# therm-hub.net
KiCad netlist of a schematic drawn in EasyEDA
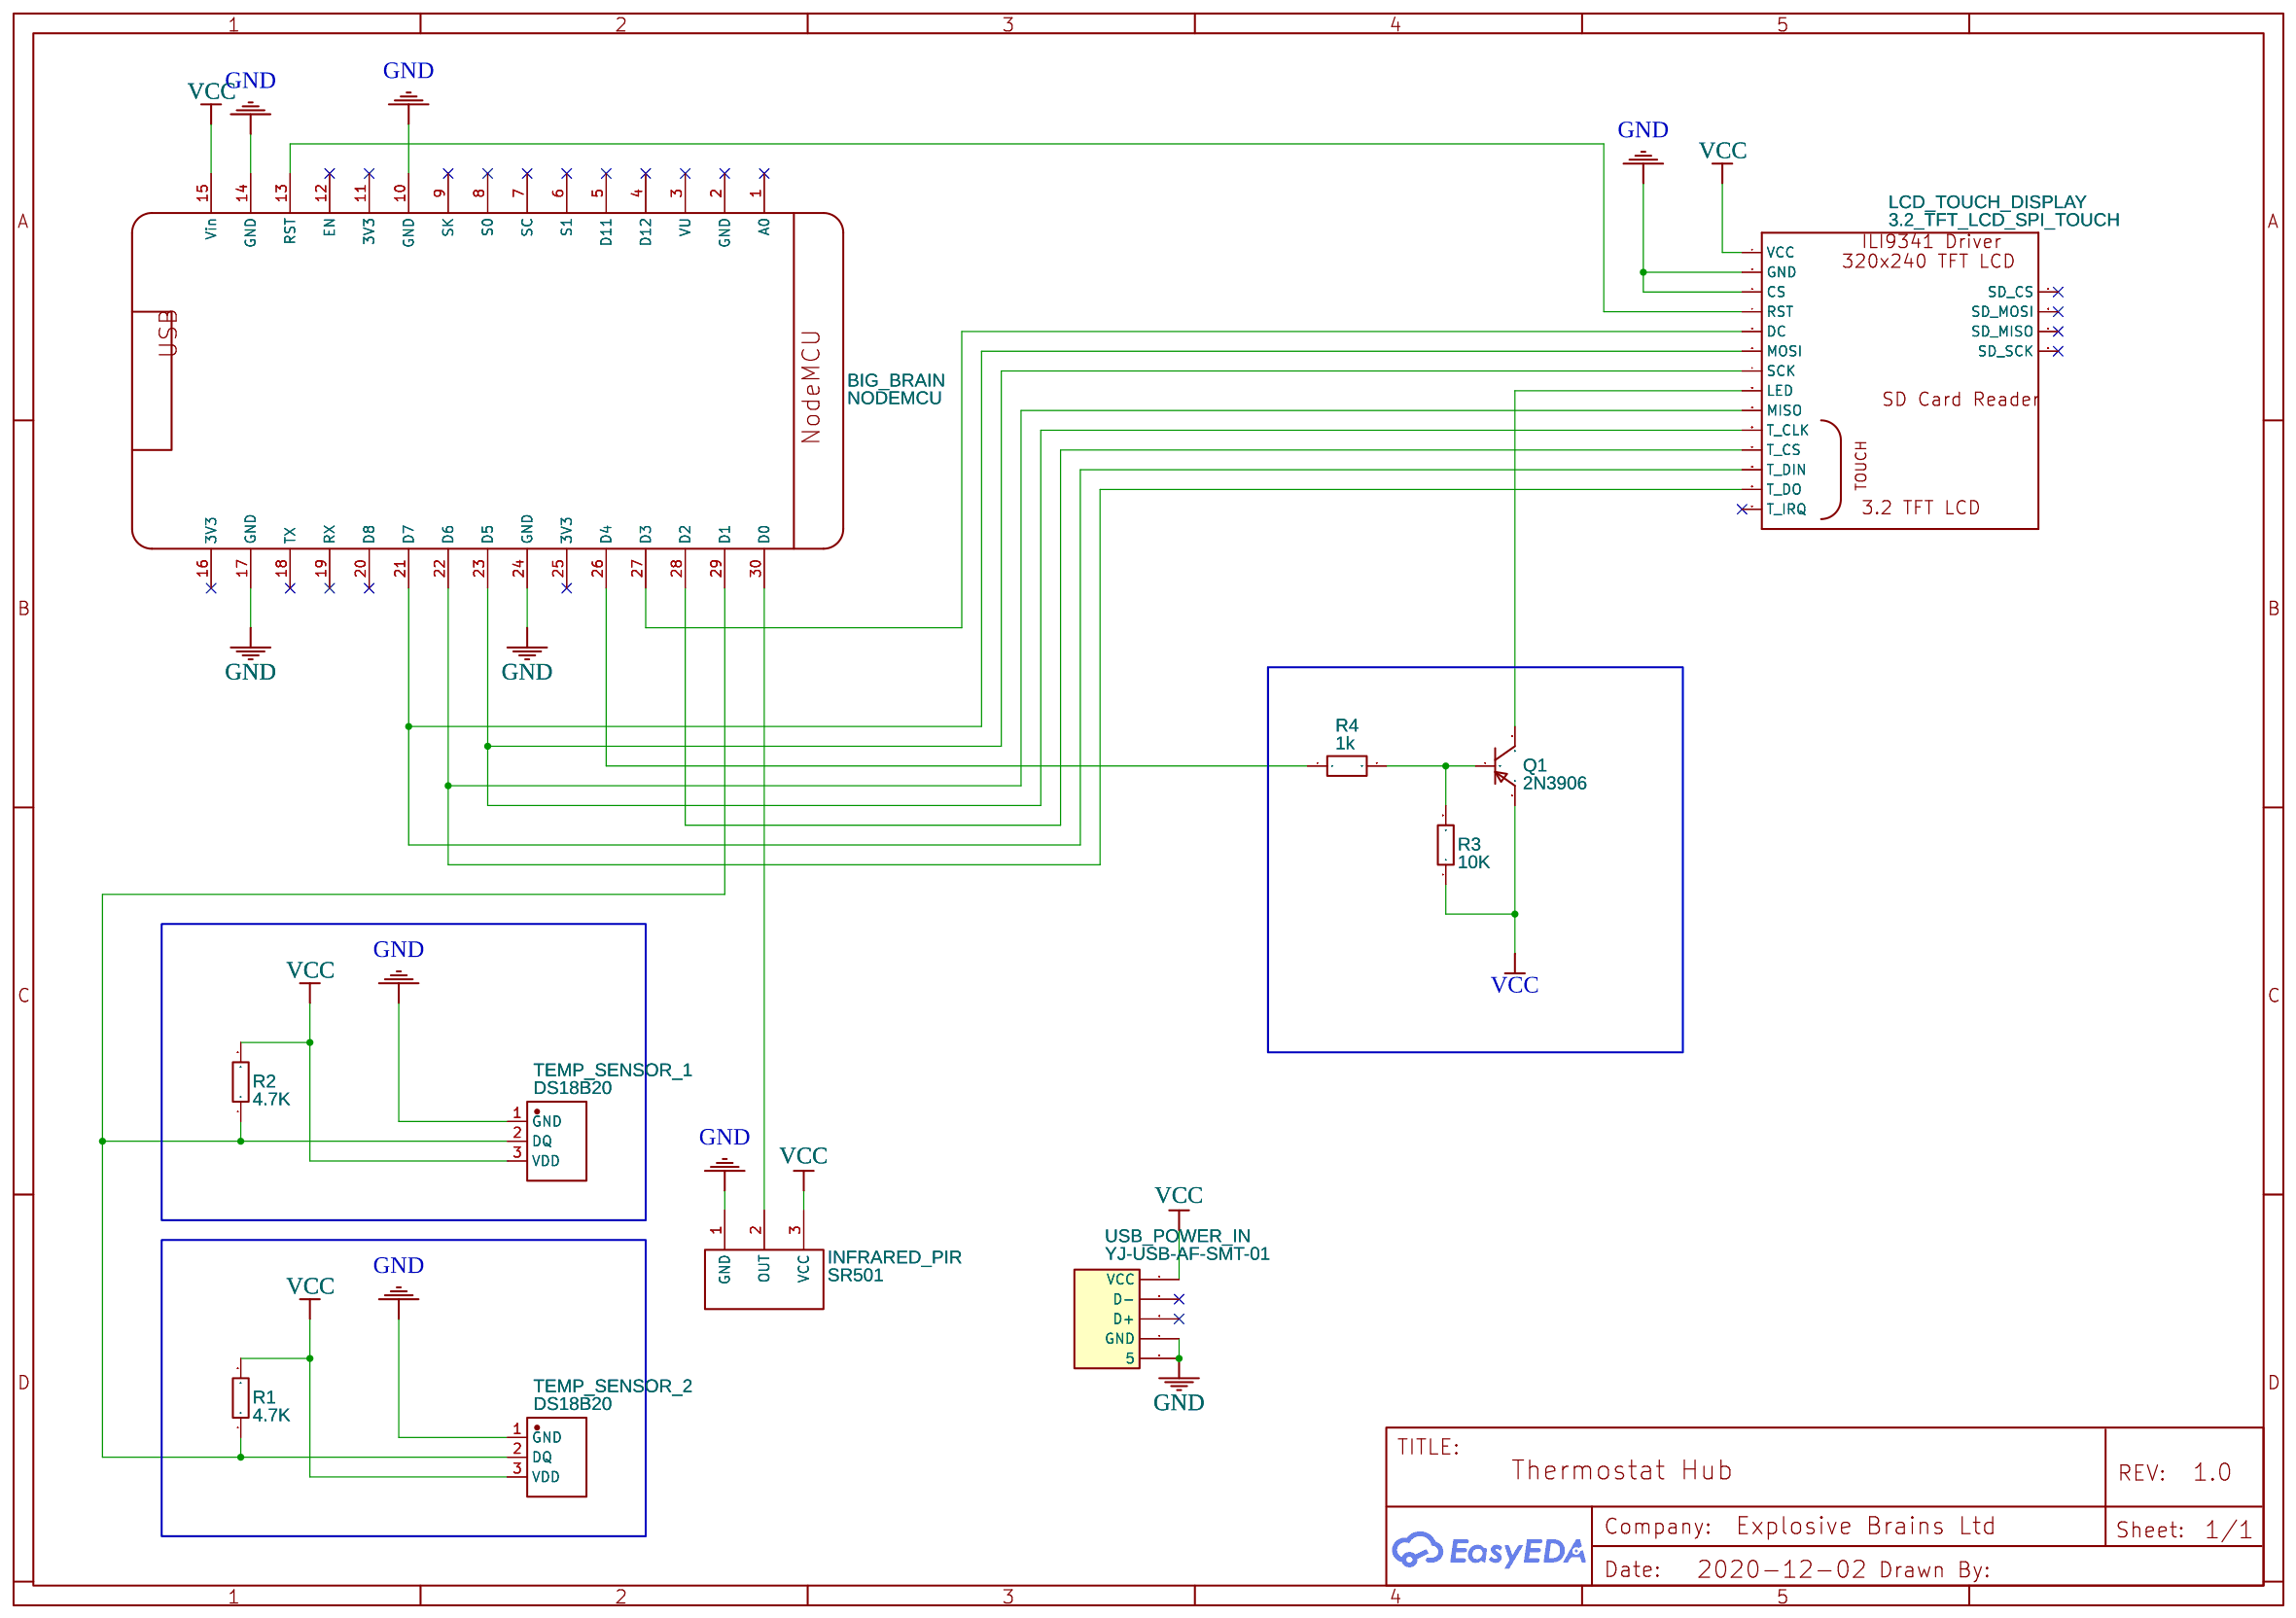
[diagram p0: schematic sheet]

(export (version "E")
  (design (tool "Eeschema 10.0.6"))
  (components
    (comp (ref "BIG_BRAIN") (value "NODEMCU") (libsource (lib "") (part "NODEMCU")))
    (comp (ref "INFRARED_PIR") (value "SR501") (libsource (lib "") (part "SR501")))
    (comp (ref "LCD_TOUCH_DISPLAY")
      (value "3.2_TFT_LCD_SPI_TOUCH")
      (libsource (lib "") (part "3.2_TFT_LCD_SPI_TOUCH"))
    )
    (comp (ref "Q1")
      (value "2N3906")
      (fields (field (name "BOM_Supplier Part") "C9809"))
      (libsource (lib "") (part "2N3906"))
    )
    (comp (ref "R1")
      (value "4.7K")
      (fields (field (name "BOM_Supplier Part") "C120071"))
      (libsource (lib "") (part "CF1/4W-4.7KΩ±5% T52"))
    )
    (comp (ref "R2")
      (value "4.7K")
      (fields (field (name "BOM_Supplier Part") "C120071"))
      (libsource (lib "") (part "CF1/4W-4.7KΩ±5% T52"))
    )
    (comp (ref "R3")
      (value "10K")
      (fields
        (field (name "BOM_Manufacturer Part") "CFR0W4J0103A50")
        (field (name "BOM_Supplier Part") "C61299")
      )
      (libsource (lib "") (part "CFR0W4J0103A50"))
    )
    (comp (ref "R4")
      (value "1k")
      (fields
        (field (name "BOM_Manufacturer Part") "CFR0W4J0102A50")
        (field (name "BOM_Supplier Part") "C66649")
      )
      (libsource (lib "") (part "CFR0W4J0102A50_C66649"))
    )
    (comp (ref "TEMP_SENSOR_1")
      (value "DS18B20")
      (fields (field (name "BOM_Supplier Part") "C376006"))
      (libsource (lib "") (part "DS18B20"))
    )
    (comp (ref "TEMP_SENSOR_2")
      (value "DS18B20")
      (fields (field (name "BOM_Supplier Part") "C376006"))
      (libsource (lib "") (part "DS18B20"))
    )
    (comp (ref "USB_POWER_IN")
      (value "YJ-USB-AF-SMT-01")
      (fields (field (name "BOM_Supplier Part") "C8328"))
      (libsource (lib "") (part "YJ-USB-AF-SMT-01"))
    )
  )
  (nets
    (net (code "1") (name "GND") (class "Default")
      (node (ref "BIG_BRAIN") (pin "10") (pinfunction "GND_10") (pintype "unspecified"))
      (node (ref "BIG_BRAIN") (pin "14") (pinfunction "GND_14") (pintype "unspecified"))
      (node (ref "BIG_BRAIN") (pin "17") (pinfunction "GND_17") (pintype "unspecified"))
      (node (ref "BIG_BRAIN") (pin "24") (pinfunction "GND_24") (pintype "unspecified"))
      (node (ref "INFRARED_PIR") (pin "1") (pinfunction "GND_1") (pintype "unspecified"))
      (node (ref "LCD_TOUCH_DISPLAY") (pin "2") (pinfunction "GND_2") (pintype "passive"))
      (node (ref "LCD_TOUCH_DISPLAY") (pin "3") (pinfunction "CS_3") (pintype "unspecified"))
      (node (ref "TEMP_SENSOR_1") (pin "1") (pinfunction "GND_1") (pintype "unspecified"))
      (node (ref "TEMP_SENSOR_2") (pin "1") (pinfunction "GND_1") (pintype "unspecified"))
      (node (ref "USB_POWER_IN") (pin "4") (pinfunction "GND_4") (pintype "input"))
      (node (ref "USB_POWER_IN") (pin "5") (pinfunction "5_5") (pintype "input"))
    )
    (net (code "2") (name "Net-(BIG_BRAIN-D0)") (class "Default")
      (node (ref "BIG_BRAIN") (pin "30") (pinfunction "D0_30") (pintype "unspecified"))
      (node (ref "INFRARED_PIR") (pin "2") (pinfunction "OUT_2") (pintype "unspecified"))
    )
    (net (code "3") (name "Net-(BIG_BRAIN-D1)") (class "Default")
      (node (ref "BIG_BRAIN") (pin "29") (pinfunction "D1_29") (pintype "unspecified"))
      (node (ref "R1") (pin "1") (pinfunction "1_1") (pintype "unspecified"))
      (node (ref "R2") (pin "1") (pinfunction "1_1") (pintype "unspecified"))
      (node (ref "TEMP_SENSOR_1") (pin "2") (pinfunction "DQ_2") (pintype "unspecified"))
      (node (ref "TEMP_SENSOR_2") (pin "2") (pinfunction "DQ_2") (pintype "unspecified"))
    )
    (net (code "4") (name "Net-(BIG_BRAIN-D2)") (class "Default")
      (node (ref "BIG_BRAIN") (pin "28") (pinfunction "D2_28") (pintype "unspecified"))
      (node (ref "LCD_TOUCH_DISPLAY") (pin "11") (pinfunction "T_CS_11") (pintype "unspecified"))
    )
    (net (code "5") (name "Net-(BIG_BRAIN-D3)") (class "Default")
      (node (ref "BIG_BRAIN") (pin "27") (pinfunction "D3_27") (pintype "unspecified"))
      (node (ref "LCD_TOUCH_DISPLAY") (pin "5") (pinfunction "DC_5") (pintype "unspecified"))
    )
    (net (code "6") (name "Net-(BIG_BRAIN-D4)") (class "Default")
      (node (ref "BIG_BRAIN") (pin "26") (pinfunction "D4_26") (pintype "unspecified"))
      (node (ref "R4") (pin "1") (pinfunction "1_1") (pintype "unspecified"))
    )
    (net (code "7") (name "Net-(BIG_BRAIN-D5)") (class "Default")
      (node (ref "BIG_BRAIN") (pin "23") (pinfunction "D5_23") (pintype "unspecified"))
      (node (ref "LCD_TOUCH_DISPLAY") (pin "10") (pinfunction "T_CLK_10") (pintype "unspecified"))
      (node (ref "LCD_TOUCH_DISPLAY") (pin "7") (pinfunction "SCK_7") (pintype "unspecified"))
    )
    (net (code "8") (name "Net-(BIG_BRAIN-D6)") (class "Default")
      (node (ref "BIG_BRAIN") (pin "22") (pinfunction "D6_22") (pintype "unspecified"))
      (node (ref "LCD_TOUCH_DISPLAY") (pin "13") (pinfunction "T_DO_13") (pintype "unspecified"))
      (node (ref "LCD_TOUCH_DISPLAY") (pin "9") (pinfunction "MISO_9") (pintype "unspecified"))
    )
    (net (code "9") (name "Net-(BIG_BRAIN-D7)") (class "Default")
      (node (ref "BIG_BRAIN") (pin "21") (pinfunction "D7_21") (pintype "unspecified"))
      (node (ref "LCD_TOUCH_DISPLAY") (pin "12") (pinfunction "T_DIN_12") (pintype "unspecified"))
      (node (ref "LCD_TOUCH_DISPLAY") (pin "6") (pinfunction "MOSI_6") (pintype "unspecified"))
    )
    (net (code "10") (name "Net-(BIG_BRAIN-RST)") (class "Default")
      (node (ref "BIG_BRAIN") (pin "13") (pinfunction "RST_13") (pintype "unspecified"))
      (node (ref "LCD_TOUCH_DISPLAY") (pin "4") (pinfunction "RST_4") (pintype "unspecified"))
    )
    (net (code "11") (name "Net-(LCD_TOUCH_DISPLAY-LED)") (class "Default")
      (node (ref "LCD_TOUCH_DISPLAY") (pin "8") (pinfunction "LED_8") (pintype "unspecified"))
      (node (ref "Q1") (pin "3") (pinfunction "C_3") (pintype "unspecified"))
    )
    (net (code "12") (name "Net-(Q1-B)") (class "Default")
      (node (ref "Q1") (pin "2") (pinfunction "B_2") (pintype "unspecified"))
      (node (ref "R3") (pin "2") (pinfunction "2_2") (pintype "input"))
      (node (ref "R4") (pin "2") (pinfunction "2_2") (pintype "unspecified"))
    )
    (net (code "13") (name "VCC") (class "Default")
      (node (ref "BIG_BRAIN") (pin "15") (pinfunction "Vin_15") (pintype "unspecified"))
      (node (ref "INFRARED_PIR") (pin "3") (pinfunction "VCC_3") (pintype "unspecified"))
      (node (ref "LCD_TOUCH_DISPLAY") (pin "1") (pinfunction "VCC_1") (pintype "passive"))
      (node (ref "Q1") (pin "1") (pinfunction "E_1") (pintype "unspecified"))
      (node (ref "R1") (pin "2") (pinfunction "2_2") (pintype "unspecified"))
      (node (ref "R2") (pin "2") (pinfunction "2_2") (pintype "unspecified"))
      (node (ref "R3") (pin "1") (pinfunction "1_1") (pintype "input"))
      (node (ref "TEMP_SENSOR_1") (pin "3") (pinfunction "VDD_3") (pintype "unspecified"))
      (node (ref "TEMP_SENSOR_2") (pin "3") (pinfunction "VDD_3") (pintype "unspecified"))
      (node (ref "USB_POWER_IN") (pin "1") (pinfunction "VCC_1") (pintype "input"))
    )
    (net (code "14") (name "unconnected-(BIG_BRAIN-3V3-Pad11)") (class "Default")
      (node (ref "BIG_BRAIN") (pin "11") (pinfunction "3V3_11") (pintype "unspecified+no_connect"))
    )
    (net (code "15") (name "unconnected-(BIG_BRAIN-3V3-Pad16)") (class "Default")
      (node (ref "BIG_BRAIN") (pin "16") (pinfunction "3V3_16") (pintype "unspecified+no_connect"))
    )
    (net (code "16") (name "unconnected-(BIG_BRAIN-3V3-Pad25)") (class "Default")
      (node (ref "BIG_BRAIN") (pin "25") (pinfunction "3V3_25") (pintype "unspecified+no_connect"))
    )
    (net (code "17") (name "unconnected-(BIG_BRAIN-A0-Pad1)") (class "Default")
      (node (ref "BIG_BRAIN") (pin "1") (pinfunction "A0_1") (pintype "unspecified+no_connect"))
    )
    (net (code "18") (name "unconnected-(BIG_BRAIN-D8-Pad20)") (class "Default")
      (node (ref "BIG_BRAIN") (pin "20") (pinfunction "D8_20") (pintype "unspecified+no_connect"))
    )
    (net (code "19") (name "unconnected-(BIG_BRAIN-D11-Pad5)") (class "Default")
      (node (ref "BIG_BRAIN") (pin "5") (pinfunction "D11_5") (pintype "unspecified+no_connect"))
    )
    (net (code "20") (name "unconnected-(BIG_BRAIN-D12-Pad4)") (class "Default")
      (node (ref "BIG_BRAIN") (pin "4") (pinfunction "D12_4") (pintype "unspecified+no_connect"))
    )
    (net (code "21") (name "unconnected-(BIG_BRAIN-EN-Pad12)") (class "Default")
      (node (ref "BIG_BRAIN") (pin "12") (pinfunction "EN_12") (pintype "unspecified+no_connect"))
    )
    (net (code "22") (name "unconnected-(BIG_BRAIN-GND-Pad2)") (class "Default")
      (node (ref "BIG_BRAIN") (pin "2") (pinfunction "GND_2") (pintype "unspecified+no_connect"))
    )
    (net (code "23") (name "unconnected-(BIG_BRAIN-RX-Pad19)") (class "Default")
      (node (ref "BIG_BRAIN") (pin "19") (pinfunction "RX_19") (pintype "unspecified+no_connect"))
    )
    (net (code "24") (name "unconnected-(BIG_BRAIN-S0-Pad8)") (class "Default")
      (node (ref "BIG_BRAIN") (pin "8") (pinfunction "S0_8") (pintype "unspecified+no_connect"))
    )
    (net (code "25") (name "unconnected-(BIG_BRAIN-S1-Pad6)") (class "Default")
      (node (ref "BIG_BRAIN") (pin "6") (pinfunction "S1_6") (pintype "unspecified+no_connect"))
    )
    (net (code "26") (name "unconnected-(BIG_BRAIN-SC-Pad7)") (class "Default")
      (node (ref "BIG_BRAIN") (pin "7") (pinfunction "SC_7") (pintype "unspecified+no_connect"))
    )
    (net (code "27") (name "unconnected-(BIG_BRAIN-SK-Pad9)") (class "Default")
      (node (ref "BIG_BRAIN") (pin "9") (pinfunction "SK_9") (pintype "unspecified+no_connect"))
    )
    (net (code "28") (name "unconnected-(BIG_BRAIN-TX-Pad18)") (class "Default")
      (node (ref "BIG_BRAIN") (pin "18") (pinfunction "TX_18") (pintype "unspecified+no_connect"))
    )
    (net (code "29") (name "unconnected-(BIG_BRAIN-VU-Pad3)") (class "Default")
      (node (ref "BIG_BRAIN") (pin "3") (pinfunction "VU_3") (pintype "unspecified+no_connect"))
    )
    (net (code "30") (name "unconnected-(LCD_TOUCH_DISPLAY-SD_CS-Pad15)") (class "Default")
      (node (ref "LCD_TOUCH_DISPLAY") (pin "15") (pinfunction "SD_CS_15") (pintype "unspecified+no_connect"))
    )
    (net (code "31") (name "unconnected-(LCD_TOUCH_DISPLAY-SD_MISO-Pad17)") (class "Default")
      (node (ref "LCD_TOUCH_DISPLAY") (pin "17") (pinfunction "SD_MISO_17") (pintype "unspecified+no_connect"))
    )
    (net (code "32") (name "unconnected-(LCD_TOUCH_DISPLAY-SD_MOSI-Pad16)") (class "Default")
      (node (ref "LCD_TOUCH_DISPLAY") (pin "16") (pinfunction "SD_MOSI_16") (pintype "unspecified+no_connect"))
    )
    (net (code "33") (name "unconnected-(LCD_TOUCH_DISPLAY-SD_SCK-Pad18)") (class "Default")
      (node (ref "LCD_TOUCH_DISPLAY") (pin "18") (pinfunction "SD_SCK_18") (pintype "unspecified+no_connect"))
    )
    (net (code "34") (name "unconnected-(LCD_TOUCH_DISPLAY-T_IRQ-Pad14)") (class "Default")
      (node (ref "LCD_TOUCH_DISPLAY") (pin "14") (pinfunction "T_IRQ_14") (pintype "unspecified+no_connect"))
    )
    (net (code "35") (name "unconnected-(USB_POWER_IN-D+-Pad3)") (class "Default")
      (node (ref "USB_POWER_IN") (pin "3") (pinfunction "D+_3") (pintype "input+no_connect"))
    )
    (net (code "36") (name "unconnected-(USB_POWER_IN-D--Pad2)") (class "Default")
      (node (ref "USB_POWER_IN") (pin "2") (pinfunction "D-_2") (pintype "input+no_connect"))
    )
  )
)
